# A3000_BigROMs.net
KiCad netlist of a schematic drawn in Altium Designer
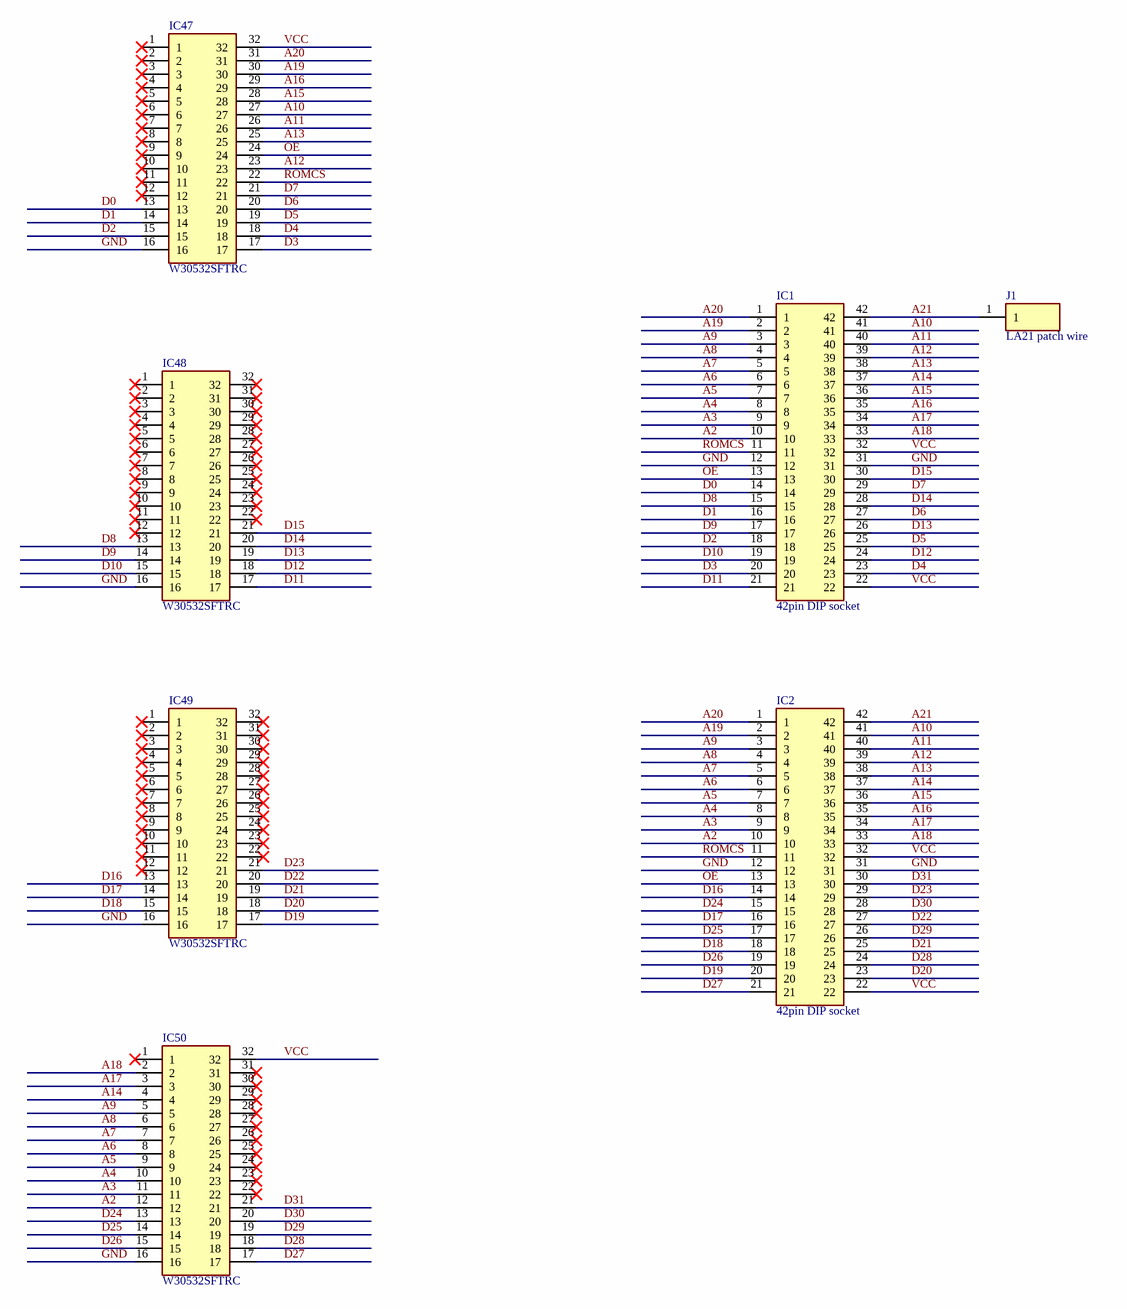
[diagram p0: A3000_BigROMs.SchDoc]

(export (version "E")
  (design (tool "Eeschema 10.0.6"))
  (components
    (comp (ref "IC1")
      (value "42pin DIP socket")
      (footprint "SamacSys:DIPS1524W50P254L5330H420Q42N")
      (description "Connector")
      (fields
        (field (name "MANUFACTURER_PART_NUMBER") "110-87-642-41-001101")
        (field (name "MOUSER PART NUMBER") "437-1108764241001101")
      )
      (libsource (lib "*") (part "110-87-642-41-001101"))
    )
    (comp (ref "IC2")
      (value "42pin DIP socket")
      (footprint "SamacSys:DIPS1524W50P254L5330H420Q42N")
      (description "Connector")
      (fields
        (field (name "MANUFACTURER_PART_NUMBER") "110-87-642-41-001101")
        (field (name "MOUSER PART NUMBER") "437-1108764241001101")
      )
      (libsource (lib "*") (part "110-87-642-41-001101"))
    )
    (comp (ref "IC47")
      (value "W30532SFTRC")
      (footprint "SamacSys:DIPS1524W55P254L4056H350Q32N")
      (description "Connector")
      (libsource (lib "*") (part "W30532SFTRC"))
    )
    (comp (ref "IC48")
      (value "W30532SFTRC")
      (footprint "SamacSys:DIPS1524W55P254L4056H350Q32N")
      (description "Connector")
      (libsource (lib "*") (part "W30532SFTRC"))
    )
    (comp (ref "IC49")
      (value "W30532SFTRC")
      (footprint "SamacSys:DIPS1524W55P254L4056H350Q32N")
      (description "Connector")
      (libsource (lib "*") (part "W30532SFTRC"))
    )
    (comp (ref "IC50")
      (value "W30532SFTRC")
      (footprint "SamacSys:DIPS1524W55P254L4056H350Q32N")
      (description "Connector")
      (libsource (lib "*") (part "W30532SFTRC"))
    )
    (comp (ref "J1")
      (value "LA21 patch wire")
      (footprint "SamacSys:TSW-101-XX-YY-S")
      (description "Connector")
      (fields
        (field (name "MANUFACTURER_PART_NUMBER") "TSW-101-07-G-S")
        (field (name "MOUSER PART NUMBER") "200-TSW10107GS")
      )
      (libsource (lib "SamacSys") (part "TSW-101-07-G-S"))
    )
  )
  (nets
    (net (code "1") (name "/A2") (class "Default")
      (node (ref "IC1") (pin "10") (pinfunction "10_10") (pintype "passive"))
      (node (ref "IC2") (pin "10") (pinfunction "10_10") (pintype "passive"))
      (node (ref "IC50") (pin "12") (pinfunction "12_12") (pintype "passive"))
    )
    (net (code "2") (name "/A3") (class "Default")
      (node (ref "IC1") (pin "9") (pinfunction "9_9") (pintype "passive"))
      (node (ref "IC2") (pin "9") (pinfunction "9_9") (pintype "passive"))
      (node (ref "IC50") (pin "11") (pinfunction "11_11") (pintype "passive"))
    )
    (net (code "3") (name "/A4") (class "Default")
      (node (ref "IC1") (pin "8") (pinfunction "8_8") (pintype "passive"))
      (node (ref "IC2") (pin "8") (pinfunction "8_8") (pintype "passive"))
      (node (ref "IC50") (pin "10") (pinfunction "10_10") (pintype "passive"))
    )
    (net (code "4") (name "/A5") (class "Default")
      (node (ref "IC1") (pin "7") (pinfunction "7_7") (pintype "passive"))
      (node (ref "IC2") (pin "7") (pinfunction "7_7") (pintype "passive"))
      (node (ref "IC50") (pin "9") (pinfunction "9_9") (pintype "passive"))
    )
    (net (code "5") (name "/A6") (class "Default")
      (node (ref "IC1") (pin "6") (pinfunction "6_6") (pintype "passive"))
      (node (ref "IC2") (pin "6") (pinfunction "6_6") (pintype "passive"))
      (node (ref "IC50") (pin "8") (pinfunction "8_8") (pintype "passive"))
    )
    (net (code "6") (name "/A7") (class "Default")
      (node (ref "IC1") (pin "5") (pinfunction "5_5") (pintype "passive"))
      (node (ref "IC2") (pin "5") (pinfunction "5_5") (pintype "passive"))
      (node (ref "IC50") (pin "7") (pinfunction "7_7") (pintype "passive"))
    )
    (net (code "7") (name "/A8") (class "Default")
      (node (ref "IC1") (pin "4") (pinfunction "4_4") (pintype "passive"))
      (node (ref "IC2") (pin "4") (pinfunction "4_4") (pintype "passive"))
      (node (ref "IC50") (pin "6") (pinfunction "6_6") (pintype "passive"))
    )
    (net (code "8") (name "/A9") (class "Default")
      (node (ref "IC1") (pin "3") (pinfunction "3_3") (pintype "passive"))
      (node (ref "IC2") (pin "3") (pinfunction "3_3") (pintype "passive"))
      (node (ref "IC50") (pin "5") (pinfunction "5_5") (pintype "passive"))
    )
    (net (code "9") (name "/A10") (class "Default")
      (node (ref "IC1") (pin "41") (pinfunction "41_41") (pintype "passive"))
      (node (ref "IC2") (pin "41") (pinfunction "41_41") (pintype "passive"))
      (node (ref "IC47") (pin "27") (pinfunction "27_27") (pintype "passive"))
    )
    (net (code "10") (name "/A11") (class "Default")
      (node (ref "IC1") (pin "40") (pinfunction "40_40") (pintype "passive"))
      (node (ref "IC2") (pin "40") (pinfunction "40_40") (pintype "passive"))
      (node (ref "IC47") (pin "26") (pinfunction "26_26") (pintype "passive"))
    )
    (net (code "11") (name "/A12") (class "Default")
      (node (ref "IC1") (pin "39") (pinfunction "39_39") (pintype "passive"))
      (node (ref "IC2") (pin "39") (pinfunction "39_39") (pintype "passive"))
      (node (ref "IC47") (pin "23") (pinfunction "23_23") (pintype "passive"))
    )
    (net (code "12") (name "/A13") (class "Default")
      (node (ref "IC1") (pin "38") (pinfunction "38_38") (pintype "passive"))
      (node (ref "IC2") (pin "38") (pinfunction "38_38") (pintype "passive"))
      (node (ref "IC47") (pin "25") (pinfunction "25_25") (pintype "passive"))
    )
    (net (code "13") (name "/A14") (class "Default")
      (node (ref "IC1") (pin "37") (pinfunction "37_37") (pintype "passive"))
      (node (ref "IC2") (pin "37") (pinfunction "37_37") (pintype "passive"))
      (node (ref "IC50") (pin "4") (pinfunction "4_4") (pintype "passive"))
    )
    (net (code "14") (name "/A15") (class "Default")
      (node (ref "IC1") (pin "36") (pinfunction "36_36") (pintype "passive"))
      (node (ref "IC2") (pin "36") (pinfunction "36_36") (pintype "passive"))
      (node (ref "IC47") (pin "28") (pinfunction "28_28") (pintype "passive"))
    )
    (net (code "15") (name "/A16") (class "Default")
      (node (ref "IC1") (pin "35") (pinfunction "35_35") (pintype "passive"))
      (node (ref "IC2") (pin "35") (pinfunction "35_35") (pintype "passive"))
      (node (ref "IC47") (pin "29") (pinfunction "29_29") (pintype "passive"))
    )
    (net (code "16") (name "/A17") (class "Default")
      (node (ref "IC1") (pin "34") (pinfunction "34_34") (pintype "passive"))
      (node (ref "IC2") (pin "34") (pinfunction "34_34") (pintype "passive"))
      (node (ref "IC50") (pin "3") (pinfunction "3_3") (pintype "passive"))
    )
    (net (code "17") (name "/A18") (class "Default")
      (node (ref "IC1") (pin "33") (pinfunction "33_33") (pintype "passive"))
      (node (ref "IC2") (pin "33") (pinfunction "33_33") (pintype "passive"))
      (node (ref "IC50") (pin "2") (pinfunction "2_2") (pintype "passive"))
    )
    (net (code "18") (name "/A19") (class "Default")
      (node (ref "IC1") (pin "2") (pinfunction "2_2") (pintype "passive"))
      (node (ref "IC2") (pin "2") (pinfunction "2_2") (pintype "passive"))
      (node (ref "IC47") (pin "30") (pinfunction "30_30") (pintype "passive"))
    )
    (net (code "19") (name "/A20") (class "Default")
      (node (ref "IC1") (pin "1") (pinfunction "1_1") (pintype "passive"))
      (node (ref "IC2") (pin "1") (pinfunction "1_1") (pintype "passive"))
      (node (ref "IC47") (pin "31") (pinfunction "31_31") (pintype "passive"))
    )
    (net (code "20") (name "/A21") (class "Default")
      (node (ref "IC1") (pin "42") (pinfunction "42_42") (pintype "passive"))
      (node (ref "IC2") (pin "42") (pinfunction "42_42") (pintype "passive"))
      (node (ref "J1") (pin "1") (pinfunction "1_1") (pintype "passive"))
    )
    (net (code "21") (name "/D0") (class "Default")
      (node (ref "IC1") (pin "14") (pinfunction "14_14") (pintype "passive"))
      (node (ref "IC47") (pin "13") (pinfunction "13_13") (pintype "passive"))
    )
    (net (code "22") (name "/D1") (class "Default")
      (node (ref "IC1") (pin "16") (pinfunction "16_16") (pintype "passive"))
      (node (ref "IC47") (pin "14") (pinfunction "14_14") (pintype "passive"))
    )
    (net (code "23") (name "/D2") (class "Default")
      (node (ref "IC1") (pin "18") (pinfunction "18_18") (pintype "passive"))
      (node (ref "IC47") (pin "15") (pinfunction "15_15") (pintype "passive"))
    )
    (net (code "24") (name "/D3") (class "Default")
      (node (ref "IC1") (pin "20") (pinfunction "20_20") (pintype "passive"))
      (node (ref "IC47") (pin "17") (pinfunction "17_17") (pintype "passive"))
    )
    (net (code "25") (name "/D4") (class "Default")
      (node (ref "IC1") (pin "23") (pinfunction "23_23") (pintype "passive"))
      (node (ref "IC47") (pin "18") (pinfunction "18_18") (pintype "passive"))
    )
    (net (code "26") (name "/D5") (class "Default")
      (node (ref "IC1") (pin "25") (pinfunction "25_25") (pintype "passive"))
      (node (ref "IC47") (pin "19") (pinfunction "19_19") (pintype "passive"))
    )
    (net (code "27") (name "/D6") (class "Default")
      (node (ref "IC1") (pin "27") (pinfunction "27_27") (pintype "passive"))
      (node (ref "IC47") (pin "20") (pinfunction "20_20") (pintype "passive"))
    )
    (net (code "28") (name "/D7") (class "Default")
      (node (ref "IC1") (pin "29") (pinfunction "29_29") (pintype "passive"))
      (node (ref "IC47") (pin "21") (pinfunction "21_21") (pintype "passive"))
    )
    (net (code "29") (name "/D8") (class "Default")
      (node (ref "IC1") (pin "15") (pinfunction "15_15") (pintype "passive"))
      (node (ref "IC48") (pin "13") (pinfunction "13_13") (pintype "passive"))
    )
    (net (code "30") (name "/D9") (class "Default")
      (node (ref "IC1") (pin "17") (pinfunction "17_17") (pintype "passive"))
      (node (ref "IC48") (pin "14") (pinfunction "14_14") (pintype "passive"))
    )
    (net (code "31") (name "/D10") (class "Default")
      (node (ref "IC1") (pin "19") (pinfunction "19_19") (pintype "passive"))
      (node (ref "IC48") (pin "15") (pinfunction "15_15") (pintype "passive"))
    )
    (net (code "32") (name "/D11") (class "Default")
      (node (ref "IC1") (pin "21") (pinfunction "21_21") (pintype "passive"))
      (node (ref "IC48") (pin "17") (pinfunction "17_17") (pintype "passive"))
    )
    (net (code "33") (name "/D12") (class "Default")
      (node (ref "IC1") (pin "24") (pinfunction "24_24") (pintype "passive"))
      (node (ref "IC48") (pin "18") (pinfunction "18_18") (pintype "passive"))
    )
    (net (code "34") (name "/D13") (class "Default")
      (node (ref "IC1") (pin "26") (pinfunction "26_26") (pintype "passive"))
      (node (ref "IC48") (pin "19") (pinfunction "19_19") (pintype "passive"))
    )
    (net (code "35") (name "/D14") (class "Default")
      (node (ref "IC1") (pin "28") (pinfunction "28_28") (pintype "passive"))
      (node (ref "IC48") (pin "20") (pinfunction "20_20") (pintype "passive"))
    )
    (net (code "36") (name "/D15") (class "Default")
      (node (ref "IC1") (pin "30") (pinfunction "30_30") (pintype "passive"))
      (node (ref "IC48") (pin "21") (pinfunction "21_21") (pintype "passive"))
    )
    (net (code "37") (name "/D16") (class "Default")
      (node (ref "IC2") (pin "14") (pinfunction "14_14") (pintype "passive"))
      (node (ref "IC49") (pin "13") (pinfunction "13_13") (pintype "passive"))
    )
    (net (code "38") (name "/D17") (class "Default")
      (node (ref "IC2") (pin "16") (pinfunction "16_16") (pintype "passive"))
      (node (ref "IC49") (pin "14") (pinfunction "14_14") (pintype "passive"))
    )
    (net (code "39") (name "/D18") (class "Default")
      (node (ref "IC2") (pin "18") (pinfunction "18_18") (pintype "passive"))
      (node (ref "IC49") (pin "15") (pinfunction "15_15") (pintype "passive"))
    )
    (net (code "40") (name "/D19") (class "Default")
      (node (ref "IC2") (pin "20") (pinfunction "20_20") (pintype "passive"))
      (node (ref "IC49") (pin "17") (pinfunction "17_17") (pintype "passive"))
    )
    (net (code "41") (name "/D20") (class "Default")
      (node (ref "IC2") (pin "23") (pinfunction "23_23") (pintype "passive"))
      (node (ref "IC49") (pin "18") (pinfunction "18_18") (pintype "passive"))
    )
    (net (code "42") (name "/D21") (class "Default")
      (node (ref "IC2") (pin "25") (pinfunction "25_25") (pintype "passive"))
      (node (ref "IC49") (pin "19") (pinfunction "19_19") (pintype "passive"))
    )
    (net (code "43") (name "/D22") (class "Default")
      (node (ref "IC2") (pin "27") (pinfunction "27_27") (pintype "passive"))
      (node (ref "IC49") (pin "20") (pinfunction "20_20") (pintype "passive"))
    )
    (net (code "44") (name "/D23") (class "Default")
      (node (ref "IC2") (pin "29") (pinfunction "29_29") (pintype "passive"))
      (node (ref "IC49") (pin "21") (pinfunction "21_21") (pintype "passive"))
    )
    (net (code "45") (name "/D24") (class "Default")
      (node (ref "IC2") (pin "15") (pinfunction "15_15") (pintype "passive"))
      (node (ref "IC50") (pin "13") (pinfunction "13_13") (pintype "passive"))
    )
    (net (code "46") (name "/D25") (class "Default")
      (node (ref "IC2") (pin "17") (pinfunction "17_17") (pintype "passive"))
      (node (ref "IC50") (pin "14") (pinfunction "14_14") (pintype "passive"))
    )
    (net (code "47") (name "/D26") (class "Default")
      (node (ref "IC2") (pin "19") (pinfunction "19_19") (pintype "passive"))
      (node (ref "IC50") (pin "15") (pinfunction "15_15") (pintype "passive"))
    )
    (net (code "48") (name "/D27") (class "Default")
      (node (ref "IC2") (pin "21") (pinfunction "21_21") (pintype "passive"))
      (node (ref "IC50") (pin "17") (pinfunction "17_17") (pintype "passive"))
    )
    (net (code "49") (name "/D28") (class "Default")
      (node (ref "IC2") (pin "24") (pinfunction "24_24") (pintype "passive"))
      (node (ref "IC50") (pin "18") (pinfunction "18_18") (pintype "passive"))
    )
    (net (code "50") (name "/D29") (class "Default")
      (node (ref "IC2") (pin "26") (pinfunction "26_26") (pintype "passive"))
      (node (ref "IC50") (pin "19") (pinfunction "19_19") (pintype "passive"))
    )
    (net (code "51") (name "/D30") (class "Default")
      (node (ref "IC2") (pin "28") (pinfunction "28_28") (pintype "passive"))
      (node (ref "IC50") (pin "20") (pinfunction "20_20") (pintype "passive"))
    )
    (net (code "52") (name "/D31") (class "Default")
      (node (ref "IC2") (pin "30") (pinfunction "30_30") (pintype "passive"))
      (node (ref "IC50") (pin "21") (pinfunction "21_21") (pintype "passive"))
    )
    (net (code "53") (name "/GND") (class "Default")
      (node (ref "IC1") (pin "12") (pinfunction "12_12") (pintype "passive"))
      (node (ref "IC1") (pin "31") (pinfunction "31_31") (pintype "passive"))
      (node (ref "IC2") (pin "12") (pinfunction "12_12") (pintype "passive"))
      (node (ref "IC2") (pin "31") (pinfunction "31_31") (pintype "passive"))
      (node (ref "IC47") (pin "16") (pinfunction "16_16") (pintype "passive"))
      (node (ref "IC48") (pin "16") (pinfunction "16_16") (pintype "passive"))
      (node (ref "IC49") (pin "16") (pinfunction "16_16") (pintype "passive"))
      (node (ref "IC50") (pin "16") (pinfunction "16_16") (pintype "passive"))
    )
    (net (code "54") (name "/OE") (class "Default")
      (node (ref "IC1") (pin "13") (pinfunction "13_13") (pintype "passive"))
      (node (ref "IC2") (pin "13") (pinfunction "13_13") (pintype "passive"))
      (node (ref "IC47") (pin "24") (pinfunction "24_24") (pintype "passive"))
    )
    (net (code "55") (name "/ROMCS") (class "Default")
      (node (ref "IC1") (pin "11") (pinfunction "11_11") (pintype "passive"))
      (node (ref "IC2") (pin "11") (pinfunction "11_11") (pintype "passive"))
      (node (ref "IC47") (pin "22") (pinfunction "22_22") (pintype "passive"))
    )
    (net (code "56") (name "/VCC") (class "Default")
      (node (ref "IC1") (pin "22") (pinfunction "22_22") (pintype "passive"))
      (node (ref "IC1") (pin "32") (pinfunction "32_32") (pintype "passive"))
      (node (ref "IC2") (pin "22") (pinfunction "22_22") (pintype "passive"))
      (node (ref "IC2") (pin "32") (pinfunction "32_32") (pintype "passive"))
      (node (ref "IC47") (pin "32") (pinfunction "32_32") (pintype "passive"))
      (node (ref "IC50") (pin "32") (pinfunction "32_32") (pintype "passive"))
    )
    (net (code "57") (name "unconnected-(IC47-Pad1)") (class "Default")
      (node (ref "IC47") (pin "1") (pinfunction "1_1") (pintype "passive+no_connect"))
    )
    (net (code "58") (name "unconnected-(IC47-Pad2)") (class "Default")
      (node (ref "IC47") (pin "2") (pinfunction "2_2") (pintype "passive+no_connect"))
    )
    (net (code "59") (name "unconnected-(IC47-Pad3)") (class "Default")
      (node (ref "IC47") (pin "3") (pinfunction "3_3") (pintype "passive+no_connect"))
    )
    (net (code "60") (name "unconnected-(IC47-Pad4)") (class "Default")
      (node (ref "IC47") (pin "4") (pinfunction "4_4") (pintype "passive+no_connect"))
    )
    (net (code "61") (name "unconnected-(IC47-Pad5)") (class "Default")
      (node (ref "IC47") (pin "5") (pinfunction "5_5") (pintype "passive+no_connect"))
    )
    (net (code "62") (name "unconnected-(IC47-Pad6)") (class "Default")
      (node (ref "IC47") (pin "6") (pinfunction "6_6") (pintype "passive+no_connect"))
    )
    (net (code "63") (name "unconnected-(IC47-Pad7)") (class "Default")
      (node (ref "IC47") (pin "7") (pinfunction "7_7") (pintype "passive+no_connect"))
    )
    (net (code "64") (name "unconnected-(IC47-Pad8)") (class "Default")
      (node (ref "IC47") (pin "8") (pinfunction "8_8") (pintype "passive+no_connect"))
    )
    (net (code "65") (name "unconnected-(IC47-Pad9)") (class "Default")
      (node (ref "IC47") (pin "9") (pinfunction "9_9") (pintype "passive+no_connect"))
    )
    (net (code "66") (name "unconnected-(IC47-Pad10)") (class "Default")
      (node (ref "IC47") (pin "10") (pinfunction "10_10") (pintype "passive+no_connect"))
    )
    (net (code "67") (name "unconnected-(IC47-Pad11)") (class "Default")
      (node (ref "IC47") (pin "11") (pinfunction "11_11") (pintype "passive+no_connect"))
    )
    (net (code "68") (name "unconnected-(IC47-Pad12)") (class "Default")
      (node (ref "IC47") (pin "12") (pinfunction "12_12") (pintype "passive+no_connect"))
    )
    (net (code "69") (name "unconnected-(IC48-Pad1)") (class "Default")
      (node (ref "IC48") (pin "1") (pinfunction "1_1") (pintype "passive+no_connect"))
    )
    (net (code "70") (name "unconnected-(IC48-Pad2)") (class "Default")
      (node (ref "IC48") (pin "2") (pinfunction "2_2") (pintype "passive+no_connect"))
    )
    (net (code "71") (name "unconnected-(IC48-Pad3)") (class "Default")
      (node (ref "IC48") (pin "3") (pinfunction "3_3") (pintype "passive+no_connect"))
    )
    (net (code "72") (name "unconnected-(IC48-Pad4)") (class "Default")
      (node (ref "IC48") (pin "4") (pinfunction "4_4") (pintype "passive+no_connect"))
    )
    (net (code "73") (name "unconnected-(IC48-Pad5)") (class "Default")
      (node (ref "IC48") (pin "5") (pinfunction "5_5") (pintype "passive+no_connect"))
    )
    (net (code "74") (name "unconnected-(IC48-Pad6)") (class "Default")
      (node (ref "IC48") (pin "6") (pinfunction "6_6") (pintype "passive+no_connect"))
    )
    (net (code "75") (name "unconnected-(IC48-Pad7)") (class "Default")
      (node (ref "IC48") (pin "7") (pinfunction "7_7") (pintype "passive+no_connect"))
    )
    (net (code "76") (name "unconnected-(IC48-Pad8)") (class "Default")
      (node (ref "IC48") (pin "8") (pinfunction "8_8") (pintype "passive+no_connect"))
    )
    (net (code "77") (name "unconnected-(IC48-Pad9)") (class "Default")
      (node (ref "IC48") (pin "9") (pinfunction "9_9") (pintype "passive+no_connect"))
    )
    (net (code "78") (name "unconnected-(IC48-Pad10)") (class "Default")
      (node (ref "IC48") (pin "10") (pinfunction "10_10") (pintype "passive+no_connect"))
    )
    (net (code "79") (name "unconnected-(IC48-Pad11)") (class "Default")
      (node (ref "IC48") (pin "11") (pinfunction "11_11") (pintype "passive+no_connect"))
    )
    (net (code "80") (name "unconnected-(IC48-Pad12)") (class "Default")
      (node (ref "IC48") (pin "12") (pinfunction "12_12") (pintype "passive+no_connect"))
    )
    (net (code "81") (name "unconnected-(IC48-Pad22)") (class "Default")
      (node (ref "IC48") (pin "22") (pinfunction "22_22") (pintype "passive+no_connect"))
    )
    (net (code "82") (name "unconnected-(IC48-Pad23)") (class "Default")
      (node (ref "IC48") (pin "23") (pinfunction "23_23") (pintype "passive+no_connect"))
    )
    (net (code "83") (name "unconnected-(IC48-Pad24)") (class "Default")
      (node (ref "IC48") (pin "24") (pinfunction "24_24") (pintype "passive+no_connect"))
    )
    (net (code "84") (name "unconnected-(IC48-Pad25)") (class "Default")
      (node (ref "IC48") (pin "25") (pinfunction "25_25") (pintype "passive+no_connect"))
    )
    (net (code "85") (name "unconnected-(IC48-Pad26)") (class "Default")
      (node (ref "IC48") (pin "26") (pinfunction "26_26") (pintype "passive+no_connect"))
    )
    (net (code "86") (name "unconnected-(IC48-Pad27)") (class "Default")
      (node (ref "IC48") (pin "27") (pinfunction "27_27") (pintype "passive+no_connect"))
    )
    (net (code "87") (name "unconnected-(IC48-Pad28)") (class "Default")
      (node (ref "IC48") (pin "28") (pinfunction "28_28") (pintype "passive+no_connect"))
    )
    (net (code "88") (name "unconnected-(IC48-Pad29)") (class "Default")
      (node (ref "IC48") (pin "29") (pinfunction "29_29") (pintype "passive+no_connect"))
    )
    (net (code "89") (name "unconnected-(IC48-Pad30)") (class "Default")
      (node (ref "IC48") (pin "30") (pinfunction "30_30") (pintype "passive+no_connect"))
    )
    (net (code "90") (name "unconnected-(IC48-Pad31)") (class "Default")
      (node (ref "IC48") (pin "31") (pinfunction "31_31") (pintype "passive+no_connect"))
    )
    (net (code "91") (name "unconnected-(IC48-Pad32)") (class "Default")
      (node (ref "IC48") (pin "32") (pinfunction "32_32") (pintype "passive+no_connect"))
    )
    (net (code "92") (name "unconnected-(IC49-Pad1)") (class "Default")
      (node (ref "IC49") (pin "1") (pinfunction "1_1") (pintype "passive+no_connect"))
    )
    (net (code "93") (name "unconnected-(IC49-Pad2)") (class "Default")
      (node (ref "IC49") (pin "2") (pinfunction "2_2") (pintype "passive+no_connect"))
    )
    (net (code "94") (name "unconnected-(IC49-Pad3)") (class "Default")
      (node (ref "IC49") (pin "3") (pinfunction "3_3") (pintype "passive+no_connect"))
    )
    (net (code "95") (name "unconnected-(IC49-Pad4)") (class "Default")
      (node (ref "IC49") (pin "4") (pinfunction "4_4") (pintype "passive+no_connect"))
    )
    (net (code "96") (name "unconnected-(IC49-Pad5)") (class "Default")
      (node (ref "IC49") (pin "5") (pinfunction "5_5") (pintype "passive+no_connect"))
    )
    (net (code "97") (name "unconnected-(IC49-Pad6)") (class "Default")
      (node (ref "IC49") (pin "6") (pinfunction "6_6") (pintype "passive+no_connect"))
    )
    (net (code "98") (name "unconnected-(IC49-Pad7)") (class "Default")
      (node (ref "IC49") (pin "7") (pinfunction "7_7") (pintype "passive+no_connect"))
    )
    (net (code "99") (name "unconnected-(IC49-Pad8)") (class "Default")
      (node (ref "IC49") (pin "8") (pinfunction "8_8") (pintype "passive+no_connect"))
    )
    (net (code "100") (name "unconnected-(IC49-Pad9)") (class "Default")
      (node (ref "IC49") (pin "9") (pinfunction "9_9") (pintype "passive+no_connect"))
    )
    (net (code "101") (name "unconnected-(IC49-Pad10)") (class "Default")
      (node (ref "IC49") (pin "10") (pinfunction "10_10") (pintype "passive+no_connect"))
    )
    (net (code "102") (name "unconnected-(IC49-Pad11)") (class "Default")
      (node (ref "IC49") (pin "11") (pinfunction "11_11") (pintype "passive+no_connect"))
    )
    (net (code "103") (name "unconnected-(IC49-Pad12)") (class "Default")
      (node (ref "IC49") (pin "12") (pinfunction "12_12") (pintype "passive+no_connect"))
    )
    (net (code "104") (name "unconnected-(IC49-Pad22)") (class "Default")
      (node (ref "IC49") (pin "22") (pinfunction "22_22") (pintype "passive+no_connect"))
    )
    (net (code "105") (name "unconnected-(IC49-Pad23)") (class "Default")
      (node (ref "IC49") (pin "23") (pinfunction "23_23") (pintype "passive+no_connect"))
    )
    (net (code "106") (name "unconnected-(IC49-Pad24)") (class "Default")
      (node (ref "IC49") (pin "24") (pinfunction "24_24") (pintype "passive+no_connect"))
    )
    (net (code "107") (name "unconnected-(IC49-Pad25)") (class "Default")
      (node (ref "IC49") (pin "25") (pinfunction "25_25") (pintype "passive+no_connect"))
    )
    (net (code "108") (name "unconnected-(IC49-Pad26)") (class "Default")
      (node (ref "IC49") (pin "26") (pinfunction "26_26") (pintype "passive+no_connect"))
    )
    (net (code "109") (name "unconnected-(IC49-Pad27)") (class "Default")
      (node (ref "IC49") (pin "27") (pinfunction "27_27") (pintype "passive+no_connect"))
    )
    (net (code "110") (name "unconnected-(IC49-Pad28)") (class "Default")
      (node (ref "IC49") (pin "28") (pinfunction "28_28") (pintype "passive+no_connect"))
    )
    (net (code "111") (name "unconnected-(IC49-Pad29)") (class "Default")
      (node (ref "IC49") (pin "29") (pinfunction "29_29") (pintype "passive+no_connect"))
    )
    (net (code "112") (name "unconnected-(IC49-Pad30)") (class "Default")
      (node (ref "IC49") (pin "30") (pinfunction "30_30") (pintype "passive+no_connect"))
    )
    (net (code "113") (name "unconnected-(IC49-Pad31)") (class "Default")
      (node (ref "IC49") (pin "31") (pinfunction "31_31") (pintype "passive+no_connect"))
    )
    (net (code "114") (name "unconnected-(IC49-Pad32)") (class "Default")
      (node (ref "IC49") (pin "32") (pinfunction "32_32") (pintype "passive+no_connect"))
    )
    (net (code "115") (name "unconnected-(IC50-Pad1)") (class "Default")
      (node (ref "IC50") (pin "1") (pinfunction "1_1") (pintype "passive+no_connect"))
    )
    (net (code "116") (name "unconnected-(IC50-Pad22)") (class "Default")
      (node (ref "IC50") (pin "22") (pinfunction "22_22") (pintype "passive+no_connect"))
    )
    (net (code "117") (name "unconnected-(IC50-Pad23)") (class "Default")
      (node (ref "IC50") (pin "23") (pinfunction "23_23") (pintype "passive+no_connect"))
    )
    (net (code "118") (name "unconnected-(IC50-Pad24)") (class "Default")
      (node (ref "IC50") (pin "24") (pinfunction "24_24") (pintype "passive+no_connect"))
    )
    (net (code "119") (name "unconnected-(IC50-Pad25)") (class "Default")
      (node (ref "IC50") (pin "25") (pinfunction "25_25") (pintype "passive+no_connect"))
    )
    (net (code "120") (name "unconnected-(IC50-Pad26)") (class "Default")
      (node (ref "IC50") (pin "26") (pinfunction "26_26") (pintype "passive+no_connect"))
    )
    (net (code "121") (name "unconnected-(IC50-Pad27)") (class "Default")
      (node (ref "IC50") (pin "27") (pinfunction "27_27") (pintype "passive+no_connect"))
    )
    (net (code "122") (name "unconnected-(IC50-Pad28)") (class "Default")
      (node (ref "IC50") (pin "28") (pinfunction "28_28") (pintype "passive+no_connect"))
    )
    (net (code "123") (name "unconnected-(IC50-Pad29)") (class "Default")
      (node (ref "IC50") (pin "29") (pinfunction "29_29") (pintype "passive+no_connect"))
    )
    (net (code "124") (name "unconnected-(IC50-Pad30)") (class "Default")
      (node (ref "IC50") (pin "30") (pinfunction "30_30") (pintype "passive+no_connect"))
    )
    (net (code "125") (name "unconnected-(IC50-Pad31)") (class "Default")
      (node (ref "IC50") (pin "31") (pinfunction "31_31") (pintype "passive+no_connect"))
    )
  )
)
